# TsinghuaDoor_top.net
KiCad netlist of a schematic drawn in Altium Designer
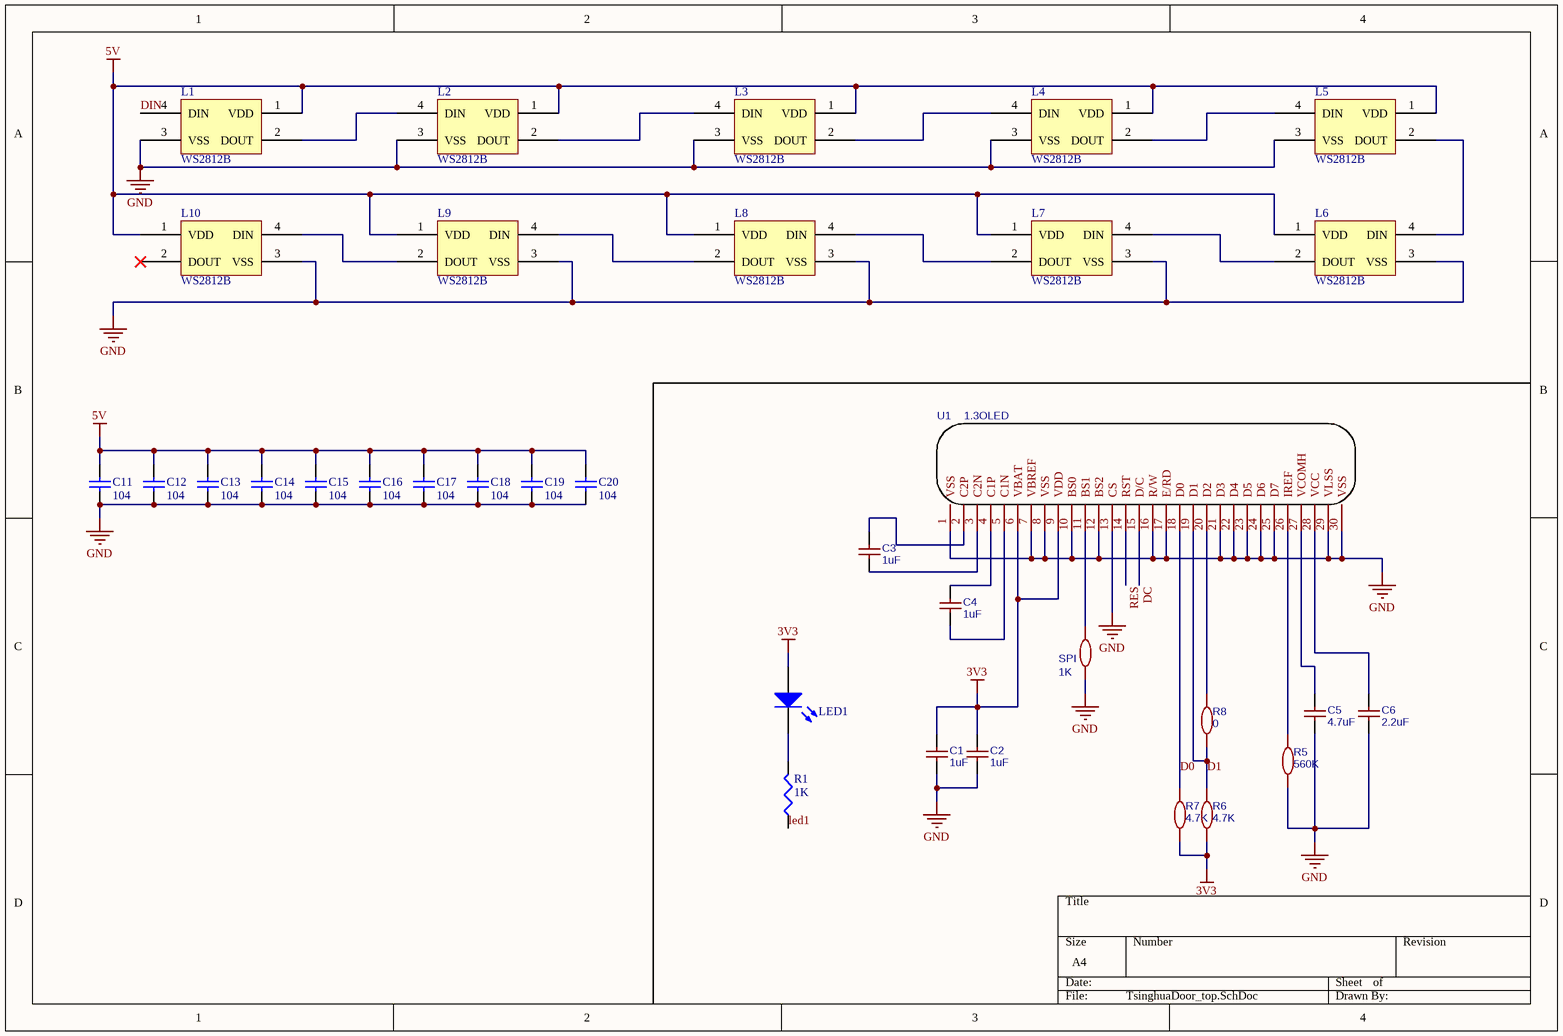
[diagram p0: TsinghuaDoor_top.SchDoc]

(export (version "E")
  (design (tool "Eeschema 10.0.6"))
  (components
    (comp (ref "C1")
      (value "1uF")
      (footprint "0805")
      (fields
        (field (name "BOM_MANUFACTURER PART") "CL21B105KBFNNNE")
        (field (name "BOM_SUPPLIER PART") "C28323")
      )
      (libsource (lib "Free Documents") (part "1uF"))
    )
    (comp (ref "C2")
      (value "1uF")
      (footprint "0805")
      (fields
        (field (name "BOM_MANUFACTURER PART") "CL21B105KBFNNNE")
        (field (name "BOM_SUPPLIER PART") "C28323")
      )
      (libsource (lib "Free Documents") (part "1uF"))
    )
    (comp (ref "C3")
      (value "1uF")
      (footprint "0805")
      (fields
        (field (name "BOM_MANUFACTURER PART") "CL21B105KBFNNNE")
        (field (name "BOM_SUPPLIER PART") "C28323")
      )
      (libsource (lib "Free Documents") (part "1uF"))
    )
    (comp (ref "C4")
      (value "1uF")
      (footprint "0805")
      (fields
        (field (name "BOM_MANUFACTURER PART") "CL21B105KBFNNNE")
        (field (name "BOM_SUPPLIER PART") "C28323")
      )
      (libsource (lib "Free Documents") (part "1uF"))
    )
    (comp (ref "C5")
      (value "4.7uF")
      (footprint "0805")
      (fields
        (field (name "BOM_MANUFACTURER PART") "CL21B105KBFNNNE")
        (field (name "BOM_SUPPLIER PART") "C28323")
      )
      (libsource (lib "Free Documents") (part "2.2uF"))
    )
    (comp (ref "C6")
      (value "2.2uF")
      (footprint "0805")
      (fields
        (field (name "BOM_MANUFACTURER PART") "CL21B105KBFNNNE")
        (field (name "BOM_SUPPLIER PART") "C28323")
      )
      (libsource (lib "Free Documents") (part "2.2uF"))
    )
    (comp (ref "C11")
      (value "104")
      (footprint "电容-0805")
      (description "Capacitor")
      (fields (field (name "Comment") "2电容") (field (name "PUBLISHER") "Altium Limited"))
      (libsource (lib "常用元件集成库") (part "2电容"))
    )
    (comp (ref "C12")
      (value "104")
      (footprint "电容-0805")
      (description "Capacitor")
      (fields (field (name "Comment") "2电容") (field (name "PUBLISHER") "Altium Limited"))
      (libsource (lib "常用元件集成库") (part "2电容"))
    )
    (comp (ref "C13")
      (value "104")
      (footprint "电容-0805")
      (description "Capacitor")
      (fields (field (name "Comment") "2电容") (field (name "PUBLISHER") "Altium Limited"))
      (libsource (lib "常用元件集成库") (part "2电容"))
    )
    (comp (ref "C14")
      (value "104")
      (footprint "电容-0805")
      (description "Capacitor")
      (fields (field (name "Comment") "2电容") (field (name "PUBLISHER") "Altium Limited"))
      (libsource (lib "常用元件集成库") (part "2电容"))
    )
    (comp (ref "C15")
      (value "104")
      (footprint "电容-0805")
      (description "Capacitor")
      (fields (field (name "Comment") "2电容") (field (name "PUBLISHER") "Altium Limited"))
      (libsource (lib "常用元件集成库") (part "2电容"))
    )
    (comp (ref "C16")
      (value "104")
      (footprint "电容-0805")
      (description "Capacitor")
      (fields (field (name "Comment") "2电容") (field (name "PUBLISHER") "Altium Limited"))
      (libsource (lib "常用元件集成库") (part "2电容"))
    )
    (comp (ref "C17")
      (value "104")
      (footprint "电容-0805")
      (description "Capacitor")
      (fields (field (name "Comment") "2电容") (field (name "PUBLISHER") "Altium Limited"))
      (libsource (lib "常用元件集成库") (part "2电容"))
    )
    (comp (ref "C18")
      (value "104")
      (footprint "电容-0805")
      (description "Capacitor")
      (fields (field (name "Comment") "2电容") (field (name "PUBLISHER") "Altium Limited"))
      (libsource (lib "常用元件集成库") (part "2电容"))
    )
    (comp (ref "C19")
      (value "104")
      (footprint "电容-0805")
      (description "Capacitor")
      (fields (field (name "Comment") "2电容") (field (name "PUBLISHER") "Altium Limited"))
      (libsource (lib "常用元件集成库") (part "2电容"))
    )
    (comp (ref "C20")
      (value "104")
      (footprint "电容-0805")
      (description "Capacitor")
      (fields (field (name "Comment") "2电容") (field (name "PUBLISHER") "Altium Limited"))
      (libsource (lib "常用元件集成库") (part "2电容"))
    )
    (comp (ref "L1") (value "WS2812B") (footprint "WS2812B") (libsource (lib "常用元件集成库") (part "WS2812B")))
    (comp (ref "L2") (value "WS2812B") (footprint "WS2812B") (libsource (lib "常用元件集成库") (part "WS2812B")))
    (comp (ref "L3") (value "WS2812B") (footprint "WS2812B") (libsource (lib "常用元件集成库") (part "WS2812B")))
    (comp (ref "L4") (value "WS2812B") (footprint "WS2812B") (libsource (lib "常用元件集成库") (part "WS2812B")))
    (comp (ref "L5") (value "WS2812B") (footprint "WS2812B") (libsource (lib "常用元件集成库") (part "WS2812B")))
    (comp (ref "L6") (value "WS2812B") (footprint "WS2812B") (libsource (lib "") (part "WS2812B_1")))
    (comp (ref "L7") (value "WS2812B") (footprint "WS2812B") (libsource (lib "") (part "WS2812B_1")))
    (comp (ref "L8") (value "WS2812B") (footprint "WS2812B") (libsource (lib "") (part "WS2812B_1")))
    (comp (ref "L9") (value "WS2812B") (footprint "WS2812B") (libsource (lib "") (part "WS2812B_1")))
    (comp (ref "L10") (value "WS2812B") (footprint "WS2812B") (libsource (lib "") (part "WS2812B_1")))
    (comp (ref "LED1")
      (value "5LED")
      (footprint "led_0603")
      (description "Typical INFRARED GaAs LED")
      (fields (field (name "PUBLISHER") "Altium Limited"))
      (libsource (lib "常用元件集成库") (part "5LED"))
    )
    (comp (ref "R1")
      (value "1K")
      (footprint "电阻_0603")
      (description "Resistor")
      (fields (field (name "Comment") "1电阻") (field (name "PUBLISHER") "Altium Limited"))
      (libsource (lib "常用元件集成库") (part "1电阻"))
    )
    (comp (ref "R5")
      (value "560K")
      (footprint "0805")
      (fields
        (field (name "BOM_SUPPLIER PART") "C60005")
        (field (name "BOM_MANUFACTURER PART") "0805W8F3922T5E")
        (field (name "CONTRIBUTOR") "hxf7582")
      )
      (libsource (lib "Free Documents") (part "560K"))
    )
    (comp (ref "R6")
      (value "4.7K")
      (footprint "0805")
      (fields
        (field (name "BOM_SUPPLIER PART") "C60005")
        (field (name "BOM_MANUFACTURER PART") "0805W8F3922T5E")
        (field (name "CONTRIBUTOR") "hxf7582")
      )
      (libsource (lib "Free Documents") (part "4.7K"))
    )
    (comp (ref "R7")
      (value "4.7K")
      (footprint "0805")
      (fields
        (field (name "BOM_SUPPLIER PART") "C60005")
        (field (name "BOM_MANUFACTURER PART") "0805W8F3922T5E")
        (field (name "CONTRIBUTOR") "hxf7582")
      )
      (libsource (lib "Free Documents") (part "4.7K"))
    )
    (comp (ref "R8")
      (value "0")
      (footprint "0805")
      (fields
        (field (name "BOM_SUPPLIER PART") "C60005")
        (field (name "BOM_MANUFACTURER PART") "0805W8F3922T5E")
        (field (name "CONTRIBUTOR") "hxf7582")
      )
      (libsource (lib "Free Documents") (part "0"))
    )
    (comp (ref "SPI")
      (value "1K")
      (footprint "0805")
      (fields
        (field (name "BOM_SUPPLIER PART") "C60005")
        (field (name "BOM_MANUFACTURER PART") "0805W8F3922T5E")
        (field (name "CONTRIBUTOR") "hxf7582")
      )
      (libsource (lib "Free Documents") (part "1K"))
    )
    (comp (ref "U1")
      (value "1.3OLED")
      (footprint "1.3-OLED-BOTTOM(CHN)")
      (fields (field (name "CONTRIBUTOR") "01bffe806c"))
      (libsource (lib "Free Documents") (part "1.3OLED"))
    )
  )
  (nets
    (net (code "1") (name "/D0") (class "Default")
      (node (ref "R7") (pin "2") (pinfunction "2_2") (pintype "passive"))
      (node (ref "U1") (pin "18") (pinfunction "D0_18") (pintype "passive"))
    )
    (net (code "2") (name "/D1") (class "Default")
      (node (ref "R6") (pin "2") (pinfunction "2_2") (pintype "passive"))
      (node (ref "R8") (pin "1") (pinfunction "1_1") (pintype "passive"))
      (node (ref "U1") (pin "19") (pinfunction "D1_19") (pintype "passive"))
    )
    (net (code "3") (name "/DC") (class "Default")
      (node (ref "U1") (pin "15") (pinfunction "D/C_15") (pintype "passive"))
    )
    (net (code "4") (name "/DIN") (class "Default")
      (node (ref "L1") (pin "4") (pinfunction "DIN_4") (pintype "passive"))
    )
    (net (code "5") (name "/RES") (class "Default")
      (node (ref "U1") (pin "14") (pinfunction "RST_14") (pintype "passive"))
    )
    (net (code "6") (name "/led1") (class "Default")
      (node (ref "R1") (pin "1") (pinfunction "1_1") (pintype "passive"))
    )
    (net (code "7") (name "3V3") (class "Default")
      (node (ref "C1") (pin "2") (pinfunction "2_2") (pintype "passive"))
      (node (ref "C2") (pin "2") (pinfunction "2_2") (pintype "passive"))
      (node (ref "LED1") (pin "1") (pinfunction "A_1") (pintype "passive"))
      (node (ref "R6") (pin "1") (pinfunction "1_1") (pintype "passive"))
      (node (ref "R7") (pin "1") (pinfunction "1_1") (pintype "passive"))
      (node (ref "U1") (pin "6") (pinfunction "VBAT_6") (pintype "passive"))
      (node (ref "U1") (pin "9") (pinfunction "VDD_9") (pintype "passive"))
    )
    (net (code "8") (name "5V") (class "Default")
      (node (ref "C11") (pin "2") (pinfunction "2_2") (pintype "passive"))
      (node (ref "C12") (pin "2") (pinfunction "2_2") (pintype "passive"))
      (node (ref "C13") (pin "2") (pinfunction "2_2") (pintype "passive"))
      (node (ref "C14") (pin "2") (pinfunction "2_2") (pintype "passive"))
      (node (ref "C15") (pin "2") (pinfunction "2_2") (pintype "passive"))
      (node (ref "C16") (pin "2") (pinfunction "2_2") (pintype "passive"))
      (node (ref "C17") (pin "2") (pinfunction "2_2") (pintype "passive"))
      (node (ref "C18") (pin "2") (pinfunction "2_2") (pintype "passive"))
      (node (ref "C19") (pin "2") (pinfunction "2_2") (pintype "passive"))
      (node (ref "C20") (pin "2") (pinfunction "2_2") (pintype "passive"))
      (node (ref "L1") (pin "1") (pinfunction "VDD_1") (pintype "passive"))
      (node (ref "L10") (pin "1") (pinfunction "VDD_1") (pintype "passive"))
      (node (ref "L2") (pin "1") (pinfunction "VDD_1") (pintype "passive"))
      (node (ref "L3") (pin "1") (pinfunction "VDD_1") (pintype "passive"))
      (node (ref "L4") (pin "1") (pinfunction "VDD_1") (pintype "passive"))
      (node (ref "L5") (pin "1") (pinfunction "VDD_1") (pintype "passive"))
      (node (ref "L6") (pin "1") (pinfunction "VDD_1") (pintype "passive"))
      (node (ref "L7") (pin "1") (pinfunction "VDD_1") (pintype "passive"))
      (node (ref "L8") (pin "1") (pinfunction "VDD_1") (pintype "passive"))
      (node (ref "L9") (pin "1") (pinfunction "VDD_1") (pintype "passive"))
    )
    (net (code "9") (name "GND") (class "Default")
      (node (ref "C1") (pin "1") (pinfunction "1_1") (pintype "passive"))
      (node (ref "C11") (pin "1") (pinfunction "1_1") (pintype "passive"))
      (node (ref "C12") (pin "1") (pinfunction "1_1") (pintype "passive"))
      (node (ref "C13") (pin "1") (pinfunction "1_1") (pintype "passive"))
      (node (ref "C14") (pin "1") (pinfunction "1_1") (pintype "passive"))
      (node (ref "C15") (pin "1") (pinfunction "1_1") (pintype "passive"))
      (node (ref "C16") (pin "1") (pinfunction "1_1") (pintype "passive"))
      (node (ref "C17") (pin "1") (pinfunction "1_1") (pintype "passive"))
      (node (ref "C18") (pin "1") (pinfunction "1_1") (pintype "passive"))
      (node (ref "C19") (pin "1") (pinfunction "1_1") (pintype "passive"))
      (node (ref "C2") (pin "1") (pinfunction "1_1") (pintype "passive"))
      (node (ref "C20") (pin "1") (pinfunction "1_1") (pintype "passive"))
      (node (ref "C5") (pin "1") (pinfunction "1_1") (pintype "passive"))
      (node (ref "C6") (pin "1") (pinfunction "1_1") (pintype "passive"))
      (node (ref "L1") (pin "3") (pinfunction "VSS_3") (pintype "passive"))
      (node (ref "L10") (pin "3") (pinfunction "VSS_3") (pintype "passive"))
      (node (ref "L2") (pin "3") (pinfunction "VSS_3") (pintype "passive"))
      (node (ref "L3") (pin "3") (pinfunction "VSS_3") (pintype "passive"))
      (node (ref "L4") (pin "3") (pinfunction "VSS_3") (pintype "passive"))
      (node (ref "L5") (pin "3") (pinfunction "VSS_3") (pintype "passive"))
      (node (ref "L6") (pin "3") (pinfunction "VSS_3") (pintype "passive"))
      (node (ref "L7") (pin "3") (pinfunction "VSS_3") (pintype "passive"))
      (node (ref "L8") (pin "3") (pinfunction "VSS_3") (pintype "passive"))
      (node (ref "L9") (pin "3") (pinfunction "VSS_3") (pintype "passive"))
      (node (ref "R5") (pin "1") (pinfunction "1_1") (pintype "passive"))
      (node (ref "SPI") (pin "1") (pinfunction "1_1") (pintype "passive"))
      (node (ref "U1") (pin "1") (pinfunction "VSS_1") (pintype "passive"))
      (node (ref "U1") (pin "10") (pinfunction "BS0_10") (pintype "passive"))
      (node (ref "U1") (pin "12") (pinfunction "BS2_12") (pintype "passive"))
      (node (ref "U1") (pin "13") (pinfunction "CS_13") (pintype "passive"))
      (node (ref "U1") (pin "16") (pinfunction "R/W_16") (pintype "passive"))
      (node (ref "U1") (pin "17") (pinfunction "E/RD_17") (pintype "passive"))
      (node (ref "U1") (pin "21") (pinfunction "D3_21") (pintype "passive"))
      (node (ref "U1") (pin "22") (pinfunction "D4_22") (pintype "passive"))
      (node (ref "U1") (pin "23") (pinfunction "D5_23") (pintype "passive"))
      (node (ref "U1") (pin "24") (pinfunction "D6_24") (pintype "passive"))
      (node (ref "U1") (pin "25") (pinfunction "D7_25") (pintype "passive"))
      (node (ref "U1") (pin "29") (pinfunction "VLSS_29") (pintype "passive"))
      (node (ref "U1") (pin "30") (pinfunction "VSS_30") (pintype "passive"))
      (node (ref "U1") (pin "7") (pinfunction "VBREF_7") (pintype "passive"))
      (node (ref "U1") (pin "8") (pinfunction "VSS_8") (pintype "passive"))
    )
    (net (code "10") (name "Net-(L1-DOUT)") (class "Default")
      (node (ref "L1") (pin "2") (pinfunction "DOUT_2") (pintype "passive"))
      (node (ref "L2") (pin "4") (pinfunction "DIN_4") (pintype "passive"))
    )
    (net (code "11") (name "Net-(L2-DOUT)") (class "Default")
      (node (ref "L2") (pin "2") (pinfunction "DOUT_2") (pintype "passive"))
      (node (ref "L3") (pin "4") (pinfunction "DIN_4") (pintype "passive"))
    )
    (net (code "12") (name "Net-(L3-DOUT)") (class "Default")
      (node (ref "L3") (pin "2") (pinfunction "DOUT_2") (pintype "passive"))
      (node (ref "L4") (pin "4") (pinfunction "DIN_4") (pintype "passive"))
    )
    (net (code "13") (name "Net-(L4-DOUT)") (class "Default")
      (node (ref "L4") (pin "2") (pinfunction "DOUT_2") (pintype "passive"))
      (node (ref "L5") (pin "4") (pinfunction "DIN_4") (pintype "passive"))
    )
    (net (code "14") (name "Net-(L5-DOUT)") (class "Default")
      (node (ref "L5") (pin "2") (pinfunction "DOUT_2") (pintype "passive"))
      (node (ref "L6") (pin "4") (pinfunction "DIN_4") (pintype "passive"))
    )
    (net (code "15") (name "Net-(L6-DOUT)") (class "Default")
      (node (ref "L6") (pin "2") (pinfunction "DOUT_2") (pintype "passive"))
      (node (ref "L7") (pin "4") (pinfunction "DIN_4") (pintype "passive"))
    )
    (net (code "16") (name "Net-(L7-DOUT)") (class "Default")
      (node (ref "L7") (pin "2") (pinfunction "DOUT_2") (pintype "passive"))
      (node (ref "L8") (pin "4") (pinfunction "DIN_4") (pintype "passive"))
    )
    (net (code "17") (name "Net-(L8-DOUT)") (class "Default")
      (node (ref "L8") (pin "2") (pinfunction "DOUT_2") (pintype "passive"))
      (node (ref "L9") (pin "4") (pinfunction "DIN_4") (pintype "passive"))
    )
    (net (code "18") (name "Net-(L10-DIN)") (class "Default")
      (node (ref "L10") (pin "4") (pinfunction "DIN_4") (pintype "passive"))
      (node (ref "L9") (pin "2") (pinfunction "DOUT_2") (pintype "passive"))
    )
    (net (code "19") (name "Net-(LED1-K)") (class "Default")
      (node (ref "LED1") (pin "2") (pinfunction "K_2") (pintype "passive"))
      (node (ref "R1") (pin "2") (pinfunction "2_2") (pintype "passive"))
    )
    (net (code "20") (name "Net-(U1-BS1)") (class "Default")
      (node (ref "SPI") (pin "2") (pinfunction "2_2") (pintype "passive"))
      (node (ref "U1") (pin "11") (pinfunction "BS1_11") (pintype "passive"))
    )
    (net (code "21") (name "Net-(U1-C1N)") (class "Default")
      (node (ref "C4") (pin "1") (pinfunction "1_1") (pintype "passive"))
      (node (ref "U1") (pin "5") (pinfunction "C1N_5") (pintype "passive"))
    )
    (net (code "22") (name "Net-(U1-C1P)") (class "Default")
      (node (ref "C4") (pin "2") (pinfunction "2_2") (pintype "passive"))
      (node (ref "U1") (pin "4") (pinfunction "C1P_4") (pintype "passive"))
    )
    (net (code "23") (name "Net-(U1-C2N)") (class "Default")
      (node (ref "C3") (pin "1") (pinfunction "1_1") (pintype "passive"))
      (node (ref "U1") (pin "3") (pinfunction "C2N_3") (pintype "passive"))
    )
    (net (code "24") (name "Net-(U1-C2P)") (class "Default")
      (node (ref "C3") (pin "2") (pinfunction "2_2") (pintype "passive"))
      (node (ref "U1") (pin "2") (pinfunction "C2P_2") (pintype "passive"))
    )
    (net (code "25") (name "Net-(U1-D2)") (class "Default")
      (node (ref "R8") (pin "2") (pinfunction "2_2") (pintype "passive"))
      (node (ref "U1") (pin "20") (pinfunction "D2_20") (pintype "passive"))
    )
    (net (code "26") (name "Net-(U1-IREF)") (class "Default")
      (node (ref "R5") (pin "2") (pinfunction "2_2") (pintype "passive"))
      (node (ref "U1") (pin "26") (pinfunction "IREF_26") (pintype "passive"))
    )
    (net (code "27") (name "Net-(U1-VCC)") (class "Default")
      (node (ref "C6") (pin "2") (pinfunction "2_2") (pintype "passive"))
      (node (ref "U1") (pin "28") (pinfunction "VCC_28") (pintype "passive"))
    )
    (net (code "28") (name "Net-(U1-VCOMH)") (class "Default")
      (node (ref "C5") (pin "2") (pinfunction "2_2") (pintype "passive"))
      (node (ref "U1") (pin "27") (pinfunction "VCOMH_27") (pintype "passive"))
    )
    (net (code "29") (name "unconnected-(L10-DOUT-Pad2)") (class "Default")
      (node (ref "L10") (pin "2") (pinfunction "DOUT_2") (pintype "passive+no_connect"))
    )
  )
)
